# CAN_IR.net
KiCad netlist of a schematic drawn in Altium Designer
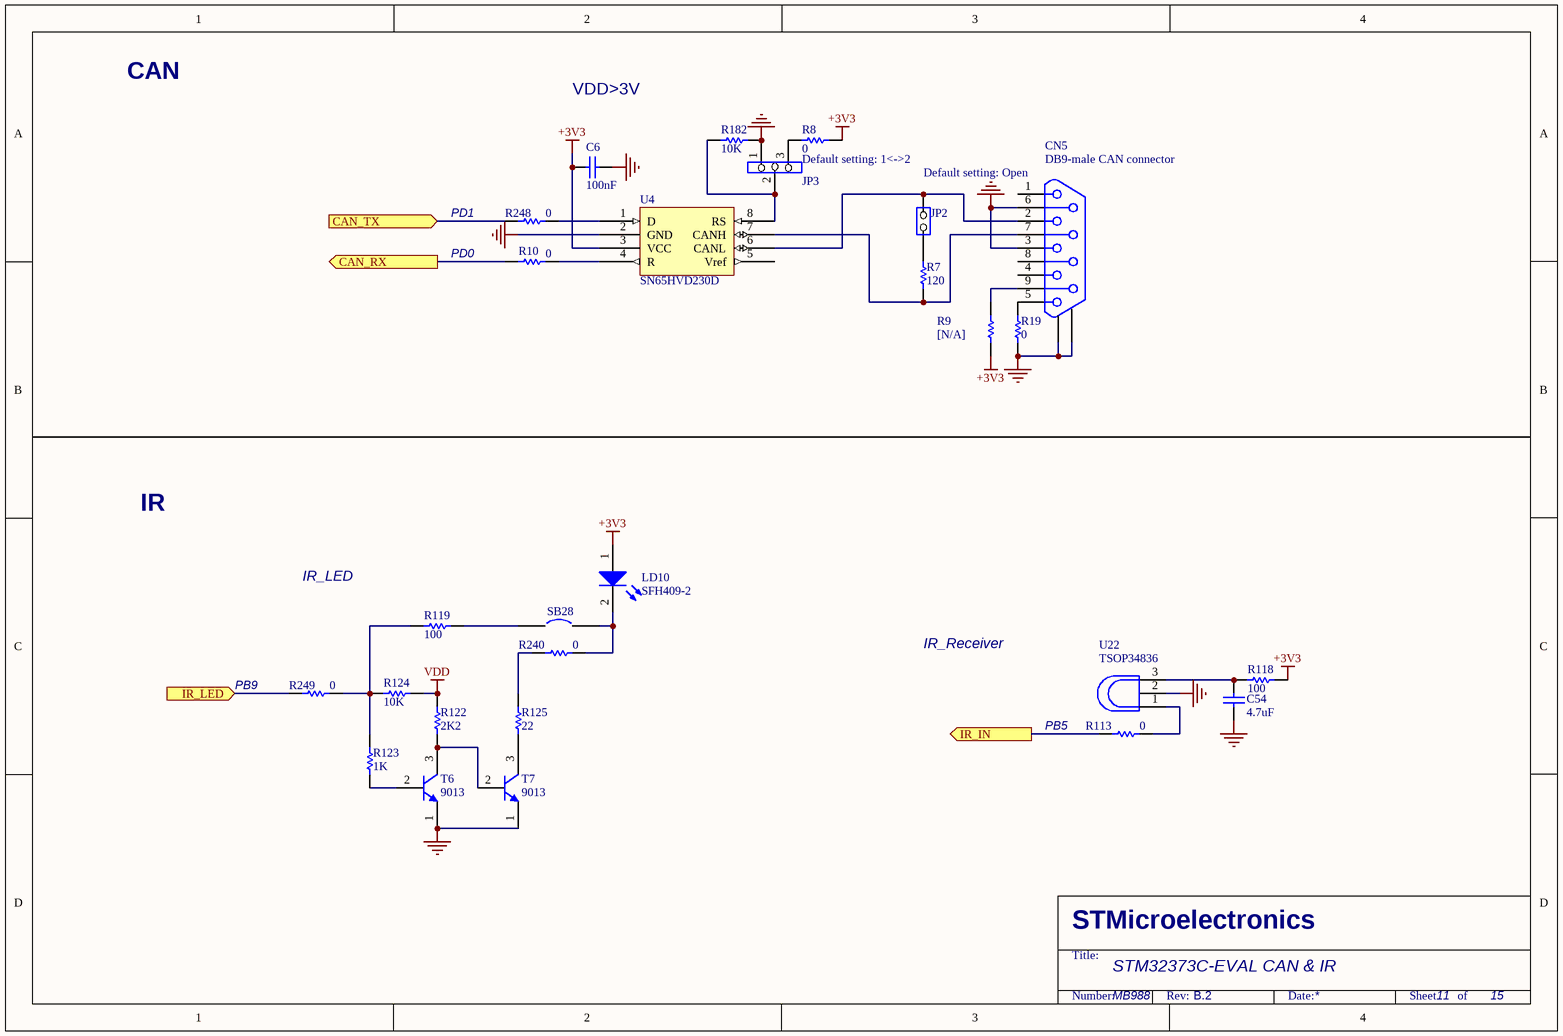
[diagram p0: CAN&IR.SchDoc]

(export (version "E")
  (design (tool "Eeschema 10.0.6"))
  (components
    (comp (ref "C6")
      (value "100nF")
      (footprint "0603C")
      (description "Capacitor")
      (fields (field (name "PUBLISHER") "Altium Limited"))
      (libsource (lib "Miscellaneous Devices") (part "CAP"))
    )
    (comp (ref "C54")
      (value "4.7uF")
      (footprint "0603C")
      (description "Capacitor")
      (fields (field (name "PUBLISHER") "Altium Limited"))
      (libsource (lib "Miscellaneous Devices") (part "Cap"))
    )
    (comp (ref "CN5") (value "DB9-male CAN connector") (footprint "DB9/M") (libsource (lib "*") (part "DB9")))
    (comp (ref "JP2") (value "~") (footprint "SIP2") (libsource (lib "*") (part "JP2")))
    (comp (ref "JP3") (value "~") (footprint "SIP3") (libsource (lib "STR910_SCHLIB") (part "Jumper3")))
    (comp (ref "LD10")
      (value "SFH409-2")
      (footprint "D0.1L")
      (description "Typical RED, GREEN, YELLOW, AMBER GaAs LED")
      (fields (field (name "PUBLISHER") "Altium Limited"))
      (libsource (lib "Miscellaneous Devices") (part "LED2"))
    )
    (comp (ref "R7")
      (value "120")
      (footprint "0603R")
      (description "Resistor")
      (fields (field (name "PUBLISHER") "Altium Limited"))
      (libsource (lib "Miscellaneous Devices") (part "res1"))
    )
    (comp (ref "R8")
      (value "0")
      (footprint "0603R")
      (description "Resistor")
      (fields (field (name "PUBLISHER") "Altium Limited"))
      (libsource (lib "Miscellaneous Devices") (part "res1"))
    )
    (comp (ref "R9")
      (value "[N/A]")
      (footprint "0603R")
      (description "Resistor")
      (fields (field (name "PUBLISHER") "Altium Limited"))
      (libsource (lib "Miscellaneous Devices") (part "res1"))
    )
    (comp (ref "R10")
      (value "0")
      (footprint "0603R")
      (description "Resistor")
      (fields (field (name "PUBLISHER") "Altium Limited"))
      (libsource (lib "Miscellaneous Devices") (part "Res1"))
    )
    (comp (ref "R19")
      (value "0")
      (footprint "0603R")
      (description "Resistor")
      (fields (field (name "PUBLISHER") "Altium Limited"))
      (libsource (lib "Miscellaneous Devices") (part "res1"))
    )
    (comp (ref "R113")
      (value "0")
      (footprint "0603R")
      (description "Resistor")
      (fields (field (name "PUBLISHER") "Altium Limited"))
      (libsource (lib "Miscellaneous Devices") (part "Res1"))
    )
    (comp (ref "R118")
      (value "100")
      (footprint "0603R")
      (description "Resistor")
      (fields (field (name "PUBLISHER") "Altium Limited"))
      (libsource (lib "Miscellaneous Devices") (part "Res1"))
    )
    (comp (ref "R119")
      (value "100")
      (footprint "0603R")
      (description "Resistor")
      (fields (field (name "PUBLISHER") "Altium Limited"))
      (libsource (lib "Miscellaneous Devices") (part "Res1"))
    )
    (comp (ref "R122")
      (value "2K2")
      (footprint "0603R")
      (description "Resistor")
      (fields (field (name "PUBLISHER") "Altium Limited"))
      (libsource (lib "Miscellaneous Devices") (part "Res1"))
    )
    (comp (ref "R123")
      (value "1K")
      (footprint "0603R")
      (description "Resistor")
      (fields (field (name "PUBLISHER") "Altium Limited"))
      (libsource (lib "Miscellaneous Devices") (part "Res1"))
    )
    (comp (ref "R124")
      (value "10K")
      (footprint "0603R")
      (description "Resistor")
      (fields (field (name "PUBLISHER") "Altium Limited"))
      (libsource (lib "Miscellaneous Devices") (part "Res1"))
    )
    (comp (ref "R125")
      (value "22")
      (footprint "0603R")
      (description "Resistor")
      (fields (field (name "PUBLISHER") "Altium Limited"))
      (libsource (lib "Miscellaneous Devices") (part "Res1"))
    )
    (comp (ref "R182")
      (value "10K")
      (footprint "0603R")
      (description "Resistor")
      (fields (field (name "PUBLISHER") "Altium Limited"))
      (libsource (lib "Miscellaneous Devices") (part "res1"))
    )
    (comp (ref "R240")
      (value "0")
      (footprint "0603R")
      (description "Resistor")
      (fields (field (name "PUBLISHER") "Altium Limited"))
      (libsource (lib "Miscellaneous Devices") (part "Res1"))
    )
    (comp (ref "R248")
      (value "0")
      (footprint "0603R")
      (description "Resistor")
      (fields (field (name "PUBLISHER") "Altium Limited"))
      (libsource (lib "Miscellaneous Devices") (part "Res1"))
    )
    (comp (ref "R249")
      (value "0")
      (footprint "0603R")
      (description "Resistor")
      (fields (field (name "PUBLISHER") "Altium Limited"))
      (libsource (lib "Miscellaneous Devices") (part "Res1"))
    )
    (comp (ref "SB28")
      (value "~")
      (footprint "JP2_SMD")
      (description "Circuit Breaker")
      (fields (field (name "PUBLISHER") "Altium Limited"))
      (libsource (lib "Miscellaneous Devices") (part "Circuit Breaker"))
    )
    (comp (ref "T6")
      (value "9013")
      (footprint "SOT-23")
      (description "NPN Bipolar Transistor")
      (fields (field (name "PUBLISHER") "Altium Limited"))
      (libsource (lib "Miscellaneous Devices") (part "NPN"))
    )
    (comp (ref "T7")
      (value "9013")
      (footprint "SOT-23")
      (description "NPN Bipolar Transistor")
      (fields (field (name "PUBLISHER") "Altium Limited"))
      (libsource (lib "Miscellaneous Devices") (part "NPN"))
    )
    (comp (ref "U4")
      (value "SN65HVD230D")
      (footprint "SO8")
      (libsource (lib "STR910_SCHLIB") (part "SN65HVD230D"))
    )
    (comp (ref "U22") (value "TSOP34836") (footprint "TSOP348") (libsource (lib "MB901") (part "TSOP34838")))
  )
  (nets
    (net (code "1") (name "+3V3") (class "Default")
      (node (ref "C6") (pin "2") (pinfunction "2_2") (pintype "passive"))
      (node (ref "LD10") (pin "1") (pinfunction "A_1") (pintype "passive"))
      (node (ref "R118") (pin "2") (pinfunction "2_2") (pintype "passive"))
      (node (ref "R8") (pin "2") (pinfunction "2_2") (pintype "passive"))
      (node (ref "R9") (pin "1") (pinfunction "1_1") (pintype "passive"))
      (node (ref "U4") (pin "3") (pinfunction "VCC_3") (pintype "power_in"))
    )
    (net (code "2") (name "/CAN_RX") (class "Default")
      (node (ref "R10") (pin "1") (pinfunction "1_1") (pintype "passive"))
    )
    (net (code "3") (name "/CAN_TX") (class "Default")
      (node (ref "R248") (pin "2") (pinfunction "2_2") (pintype "passive"))
    )
    (net (code "4") (name "/IR_IN") (class "Default")
      (node (ref "R113") (pin "1") (pinfunction "1_1") (pintype "passive"))
    )
    (net (code "5") (name "/IR_LED") (class "Default")
      (node (ref "R249") (pin "2") (pinfunction "2_2") (pintype "passive"))
    )
    (net (code "6") (name "GND") (class "Default")
      (node (ref "C54") (pin "2") (pinfunction "2_2") (pintype "passive"))
      (node (ref "C6") (pin "1") (pinfunction "1_1") (pintype "passive"))
      (node (ref "CN5") (pin "0") (pinfunction "0_0") (pintype "passive"))
      (node (ref "CN5") (pin "3") (pinfunction "3_3") (pintype "passive"))
      (node (ref "CN5") (pin "6") (pinfunction "6_6") (pintype "passive"))
      (node (ref "JP3") (pin "1") (pintype "passive"))
      (node (ref "R182") (pin "2") (pinfunction "2_2") (pintype "passive"))
      (node (ref "R19") (pin "1") (pinfunction "1_1") (pintype "passive"))
      (node (ref "T6") (pin "1") (pinfunction "E_1") (pintype "passive"))
      (node (ref "T7") (pin "1") (pinfunction "E_1") (pintype "passive"))
      (node (ref "U22") (pin "2") (pinfunction "GND_2") (pintype "passive"))
      (node (ref "U4") (pin "2") (pinfunction "GND_2") (pintype "power_in"))
    )
    (net (code "7") (name "Net-(CN5-Pad5)") (class "Default")
      (node (ref "CN5") (pin "5") (pinfunction "5_5") (pintype "passive"))
      (node (ref "R19") (pin "2") (pinfunction "2_2") (pintype "passive"))
    )
    (net (code "8") (name "Net-(CN5-Pad9)") (class "Default")
      (node (ref "CN5") (pin "9") (pinfunction "9_9") (pintype "passive"))
      (node (ref "R9") (pin "2") (pinfunction "2_2") (pintype "passive"))
    )
    (net (code "9") (name "Net-(JP2-COMMON)") (class "Default")
      (node (ref "JP2") (pin "1") (pinfunction "COMMON_1") (pintype "passive"))
      (node (ref "R7") (pin "2") (pinfunction "2_2") (pintype "passive"))
    )
    (net (code "10") (name "Net-(JP2-NO)") (class "Default")
      (node (ref "CN5") (pin "2") (pinfunction "2_2") (pintype "passive"))
      (node (ref "JP2") (pin "2") (pinfunction "NO_2") (pintype "passive"))
      (node (ref "U4") (pin "6") (pinfunction "CANL_6") (pintype "bidirectional"))
    )
    (net (code "11") (name "Net-(JP3-Pad3)") (class "Default")
      (node (ref "JP3") (pin "3") (pintype "passive"))
      (node (ref "R8") (pin "1") (pinfunction "1_1") (pintype "passive"))
    )
    (net (code "12") (name "Net-(LD10-K)") (class "Default")
      (node (ref "LD10") (pin "2") (pinfunction "K_2") (pintype "passive"))
      (node (ref "R240") (pin "2") (pinfunction "2_2") (pintype "passive"))
      (node (ref "SB28") (pin "2") (pinfunction "2_2") (pintype "passive"))
    )
    (net (code "13") (name "Net-(R119-Pad1)") (class "Default")
      (node (ref "R119") (pin "1") (pinfunction "1_1") (pintype "passive"))
      (node (ref "SB28") (pin "1") (pinfunction "1_1") (pintype "passive"))
    )
    (net (code "14") (name "Net-(R119-Pad2)") (class "Default")
      (node (ref "R119") (pin "2") (pinfunction "2_2") (pintype "passive"))
      (node (ref "R123") (pin "1") (pinfunction "1_1") (pintype "passive"))
      (node (ref "R124") (pin "2") (pinfunction "2_2") (pintype "passive"))
      (node (ref "R249") (pin "1") (pinfunction "1_1") (pintype "passive"))
    )
    (net (code "15") (name "Net-(R125-Pad2)") (class "Default")
      (node (ref "R125") (pin "2") (pinfunction "2_2") (pintype "passive"))
      (node (ref "R240") (pin "1") (pinfunction "1_1") (pintype "passive"))
    )
    (net (code "16") (name "Net-(T6-B)") (class "Default")
      (node (ref "R123") (pin "2") (pinfunction "2_2") (pintype "passive"))
      (node (ref "T6") (pin "2") (pinfunction "B_2") (pintype "passive"))
    )
    (net (code "17") (name "Net-(T6-C)") (class "Default")
      (node (ref "R122") (pin "1") (pinfunction "1_1") (pintype "passive"))
      (node (ref "T6") (pin "3") (pinfunction "C_3") (pintype "passive"))
      (node (ref "T7") (pin "2") (pinfunction "B_2") (pintype "passive"))
    )
    (net (code "18") (name "Net-(T7-C)") (class "Default")
      (node (ref "R125") (pin "1") (pinfunction "1_1") (pintype "passive"))
      (node (ref "T7") (pin "3") (pinfunction "C_3") (pintype "passive"))
    )
    (net (code "19") (name "Net-(U4-CANH)") (class "Default")
      (node (ref "CN5") (pin "7") (pinfunction "7_7") (pintype "passive"))
      (node (ref "R7") (pin "1") (pinfunction "1_1") (pintype "passive"))
      (node (ref "U4") (pin "7") (pinfunction "CANH_7") (pintype "bidirectional"))
    )
    (net (code "20") (name "Net-(U4-D)") (class "Default")
      (node (ref "R248") (pin "1") (pinfunction "1_1") (pintype "passive"))
      (node (ref "U4") (pin "1") (pinfunction "D_1") (pintype "input"))
    )
    (net (code "21") (name "Net-(U4-R)") (class "Default")
      (node (ref "R10") (pin "2") (pinfunction "2_2") (pintype "passive"))
      (node (ref "U4") (pin "4") (pinfunction "R_4") (pintype "output"))
    )
    (net (code "22") (name "Net-(U4-RS)") (class "Default")
      (node (ref "JP3") (pin "2") (pintype "passive"))
      (node (ref "R182") (pin "1") (pinfunction "1_1") (pintype "passive"))
      (node (ref "U4") (pin "8") (pinfunction "RS_8") (pintype "input"))
    )
    (net (code "23") (name "Net-(U22-OUT)") (class "Default")
      (node (ref "R113") (pin "2") (pinfunction "2_2") (pintype "passive"))
      (node (ref "U22") (pin "1") (pinfunction "OUT_1") (pintype "passive"))
    )
    (net (code "24") (name "Net-(U22-Vs)") (class "Default")
      (node (ref "C54") (pin "1") (pinfunction "1_1") (pintype "passive"))
      (node (ref "R118") (pin "1") (pinfunction "1_1") (pintype "passive"))
      (node (ref "U22") (pin "3") (pinfunction "Vs_3") (pintype "passive"))
    )
    (net (code "25") (name "VDD") (class "Default")
      (node (ref "R122") (pin "2") (pinfunction "2_2") (pintype "passive"))
      (node (ref "R124") (pin "1") (pinfunction "1_1") (pintype "passive"))
    )
    (net (code "26") (name "unconnected-(CN5-Pad1)") (class "Default")
      (node (ref "CN5") (pin "1") (pinfunction "1_1") (pintype "passive"))
    )
    (net (code "27") (name "unconnected-(CN5-Pad4)") (class "Default")
      (node (ref "CN5") (pin "4") (pinfunction "4_4") (pintype "passive"))
    )
    (net (code "28") (name "unconnected-(CN5-Pad8)") (class "Default")
      (node (ref "CN5") (pin "8") (pinfunction "8_8") (pintype "passive"))
    )
    (net (code "29") (name "unconnected-(U4-Vref-Pad5)") (class "Default")
      (node (ref "U4") (pin "5") (pinfunction "Vref_5") (pintype "output"))
    )
  )
)
